# Teeth_Radiology_SCH.net
KiCad netlist of a schematic drawn in Altium Designer
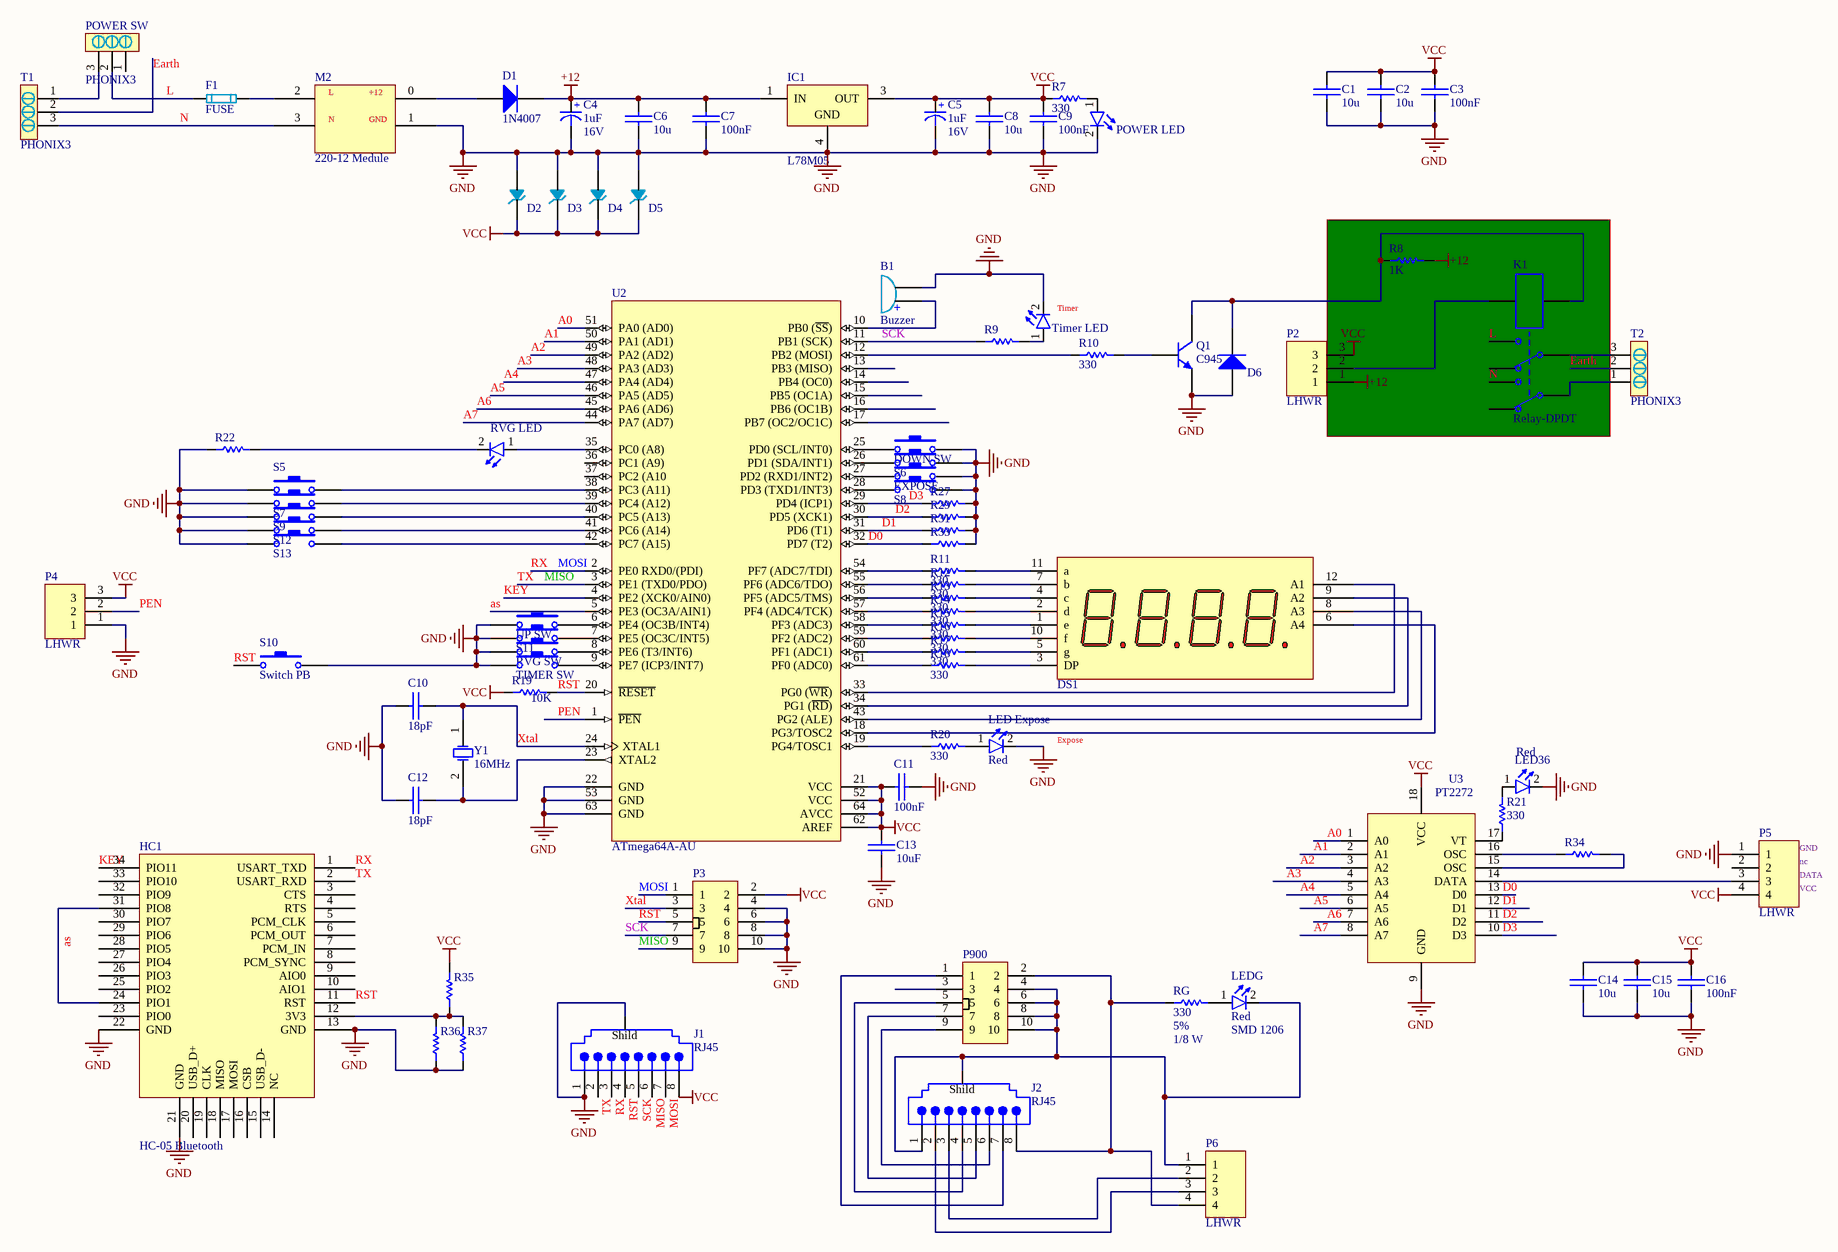
[diagram p0: Teeth_Radiology_SCH.SchDoc]

(export (version "E")
  (design (tool "Eeschema 10.0.6"))
  (components
    (comp (ref "B1")
      (value "Buzzer")
      (footprint "Buzzer")
      (fields (field (name "DESIGNER") "Hamed Jafarzadeh"))
      (libsource (lib "R2T Team Library") (part "Buzzer"))
    )
    (comp (ref "C1")
      (value "10u")
      (footprint "SMD_CAP_1206")
      (description "Bipolar Capacitor")
      (fields (field (name "VOLTAGE") "100V") (field (name "DESIGNER") "Saeid Jorablo"))
      (libsource (lib "My Library") (part "Cap-Bipolar"))
    )
    (comp (ref "C2")
      (value "10u")
      (footprint "SMD_CAP_1206")
      (description "Bipolar Capacitor")
      (fields (field (name "VOLTAGE") "100V") (field (name "DESIGNER") "Saeid Jorablo"))
      (libsource (lib "My Library") (part "Cap-Bipolar"))
    )
    (comp (ref "C3")
      (value "100nF")
      (footprint "SMD_CAP_1206")
      (description "Bipolar Capacitor")
      (fields (field (name "VOLTAGE") "100V") (field (name "DESIGNER") "Saeid Jorablo"))
      (libsource (lib "My Library") (part "Cap-Bipolar"))
    )
    (comp (ref "C4")
      (value "1uF")
      (footprint "cap 04")
      (description "Polar Capacitor")
      (fields (field (name "VOLTAGE") "16V") (field (name "DESIGNER") "Saeid Jorablo"))
      (libsource (lib "My Library") (part "Cap-Polar"))
    )
    (comp (ref "C5")
      (value "1uF")
      (footprint "cap 04")
      (description "Polar Capacitor")
      (fields (field (name "VOLTAGE") "16V") (field (name "DESIGNER") "Saeid Jorablo"))
      (libsource (lib "My Library") (part "Cap-Polar"))
    )
    (comp (ref "C6")
      (value "10u")
      (footprint "SMD_CAP_1206")
      (description "Bipolar Capacitor")
      (fields (field (name "VOLTAGE") "100V") (field (name "DESIGNER") "Saeid Jorablo"))
      (libsource (lib "My Library") (part "Cap-Bipolar"))
    )
    (comp (ref "C7")
      (value "100nF")
      (footprint "SMD_CAP_1206")
      (description "Bipolar Capacitor")
      (fields (field (name "VOLTAGE") "100V") (field (name "DESIGNER") "Saeid Jorablo"))
      (libsource (lib "My Library") (part "Cap-Bipolar"))
    )
    (comp (ref "C8")
      (value "10u")
      (footprint "SMD_CAP_1206")
      (description "Bipolar Capacitor")
      (fields (field (name "VOLTAGE") "100V") (field (name "DESIGNER") "Saeid Jorablo"))
      (libsource (lib "My Library") (part "Cap-Bipolar"))
    )
    (comp (ref "C9")
      (value "100nF")
      (footprint "SMD_CAP_1206")
      (description "Bipolar Capacitor")
      (fields (field (name "VOLTAGE") "100V") (field (name "DESIGNER") "Saeid Jorablo"))
      (libsource (lib "My Library") (part "Cap-Bipolar"))
    )
    (comp (ref "C10")
      (value "18pF")
      (footprint "SMD_CAP_0805")
      (description "Bipolar Capacitor")
      (fields (field (name "VOLTAGE") "100V") (field (name "DESIGNER") "Saeid Jorablo"))
      (libsource (lib "My Library") (part "Cap-Bipolar"))
    )
    (comp (ref "C11")
      (value "100nF")
      (footprint "SMD_CAP_0805")
      (description "Bipolar Capacitor")
      (fields (field (name "VOLTAGE") "100V") (field (name "DESIGNER") "Saeid Jorablo"))
      (libsource (lib "My Library") (part "Cap-Bipolar"))
    )
    (comp (ref "C12")
      (value "18pF")
      (footprint "SMD_CAP_0805")
      (description "Bipolar Capacitor")
      (fields (field (name "VOLTAGE") "100V") (field (name "DESIGNER") "Saeid Jorablo"))
      (libsource (lib "My Library") (part "Cap-Bipolar"))
    )
    (comp (ref "C13")
      (value "10uF")
      (footprint "SMD_CAP_1206")
      (description "Bipolar Capacitor")
      (fields (field (name "VOLTAGE") "100V") (field (name "DESIGNER") "Saeid Jorablo"))
      (libsource (lib "My Library") (part "Cap-Bipolar"))
    )
    (comp (ref "C14")
      (value "10u")
      (footprint "SMD_CAP_1206")
      (description "Bipolar Capacitor")
      (fields (field (name "VOLTAGE") "100V") (field (name "DESIGNER") "Saeid Jorablo"))
      (libsource (lib "My Library") (part "Cap-Bipolar"))
    )
    (comp (ref "C15")
      (value "10u")
      (footprint "SMD_CAP_1206")
      (description "Bipolar Capacitor")
      (fields (field (name "VOLTAGE") "100V") (field (name "DESIGNER") "Saeid Jorablo"))
      (libsource (lib "My Library") (part "Cap-Bipolar"))
    )
    (comp (ref "C16")
      (value "100nF")
      (footprint "SMD_CAP_1206")
      (description "Bipolar Capacitor")
      (fields (field (name "VOLTAGE") "100V") (field (name "DESIGNER") "Saeid Jorablo"))
      (libsource (lib "My Library") (part "Cap-Bipolar"))
    )
    (comp (ref "D1")
      (value "1N4007")
      (footprint "My_DO-41")
      (description "1 Amp Diode")
      (libsource (lib "MyAltiumLib1") (part "1N4007"))
    )
    (comp (ref "D2")
      (value "Diode Zener SMD")
      (footprint "DIOMELF3615N")
      (fields (field (name "DESIGNER") "Hamed Jafarzadeh"))
      (libsource (lib "R2T Team Library") (part "Diode Zener SMD"))
    )
    (comp (ref "D3")
      (value "Diode Zener SMD")
      (footprint "DIOMELF3615N")
      (fields (field (name "DESIGNER") "Hamed Jafarzadeh"))
      (libsource (lib "R2T Team Library") (part "Diode Zener SMD"))
    )
    (comp (ref "D4")
      (value "Diode Zener SMD")
      (footprint "DIOMELF3615N")
      (fields (field (name "DESIGNER") "Hamed Jafarzadeh"))
      (libsource (lib "R2T Team Library") (part "Diode Zener SMD"))
    )
    (comp (ref "D5")
      (value "Diode Zener SMD")
      (footprint "DIOMELF3615N")
      (fields (field (name "DESIGNER") "Hamed Jafarzadeh"))
      (libsource (lib "R2T Team Library") (part "Diode Zener SMD"))
    )
    (comp (ref "D6")
      (value "1N4007")
      (footprint "My_DO-41")
      (description "1 Amp Diode")
      (libsource (lib "MyAltiumLib1") (part "1N4007"))
    )
    (comp (ref "DOWN SW")
      (value "Switch PB")
      (footprint "Switch - Push to On")
      (description "Push Button Switch")
      (libsource (lib "Electrovolt Lib") (part "Switch PB"))
    )
    (comp (ref "DS1")
      (value "7Segment-4Digit-CA")
      (footprint "7segCA")
      (description "7-Segment Display: CA")
      (fields (field (name "PUBLISHER") "www.picpars.com") (field (name "DESIGNER") "Seyed Mohsen Ghasemain"))
      (libsource (lib "usefully_Library") (part "7Seg-4Digit-CA"))
    )
    (comp (ref "EXPOSE")
      (value "Switch PB")
      (footprint "Switch - Push to On")
      (description "Push Button Switch")
      (libsource (lib "Electrovolt Lib") (part "Switch PB"))
    )
    (comp (ref "F1") (value "FUSE") (footprint "FUSE_1") (libsource (lib "Devices") (part "FUSE")))
    (comp (ref "HC1")
      (value "HC-05 Bluetooth")
      (footprint "HC-05")
      (libsource (lib "R2T Team Library") (part "HC-05 Bluetooth"))
    )
    (comp (ref "IC1")
      (value "L78M05")
      (footprint "TO-252")
      (description "Precision 500mA Regulator")
      (libsource (lib "My Library") (part "L78M05"))
    )
    (comp (ref "J1")
      (value "RJ45")
      (footprint "My_RJ45")
      (description "Right Angle, Standard Profile, RJ45-Keyed, Flange Mount PCB Jack")
      (fields (field (name "PUBLISHER") "Altium Limited"))
      (libsource (lib "MyAltiumLib1") (part "RJ45"))
    )
    (comp (ref "J2")
      (value "RJ45")
      (footprint "My_RJ45")
      (description "Right Angle, Standard Profile, RJ45-Keyed, Flange Mount PCB Jack")
      (fields (field (name "PUBLISHER") "Altium Limited"))
      (libsource (lib "MyAltiumLib1") (part "RJ45"))
    )
    (comp (ref "K1")
      (value "Relay-DPDT")
      (footprint "My_REL_cochick")
      (description "Dual-Pole Dual-Throw Relay")
      (fields (field (name "PUBLISHER") "Altium Limited"))
      (libsource (lib "MyAltiumLib1") (part "Relay-DPDT"))
    )
    (comp (ref "LED Expose")
      (value "Red")
      (footprint "LED-3mm")
      (description "LED")
      (fields (field (name "COLOR") "Red") (field (name "DESIGNER") "Saeid Jorablo"))
      (libsource (lib "My Library") (part "LED"))
    )
    (comp (ref "LED36")
      (value "Red")
      (footprint "LED-3mm")
      (description "LED")
      (fields (field (name "COLOR") "Red") (field (name "DESIGNER") "Saeid Jorablo"))
      (libsource (lib "My Library") (part "LED"))
    )
    (comp (ref "LEDG")
      (value "Red")
      (footprint "LED-3mm")
      (description "LED")
      (fields
        (field (name "COLOR") "Red")
        (field (name "SIZE") "SMD 1206")
        (field (name "DESIGNER") "Saeid Jorablo")
      )
      (libsource (lib "My Library") (part "LED"))
    )
    (comp (ref "M2")
      (value "220-12 Medule")
      (footprint "AC-DC 220-12")
      (libsource (lib "Soga Library") (part "220-12 Medule"))
    )
    (comp (ref "P2")
      (value "LHWR")
      (footprint "Polarized Header 3")
      (fields (field (name "DESIGNER:") "Hamed Jafarzadeh - www.R2T.ir"))
      (libsource (lib "R2T Team Library") (part "3pin LHWR"))
    )
    (comp (ref "P3")
      (value "BoxHeader 2x5")
      (footprint "Box Header 2x5")
      (fields (field (name "DESIGNER") "HamedJafarzadeh - ww.R2T.ir"))
      (libsource (lib "R2T Team Library") (part "BoxHeader 2x5"))
    )
    (comp (ref "P4")
      (value "LHWR")
      (footprint "Polarized Header 3")
      (fields (field (name "DESIGNER:") "Hamed Jafarzadeh - www.R2T.ir"))
      (libsource (lib "R2T Team Library") (part "3pin LHWR"))
    )
    (comp (ref "P5")
      (value "LHWR")
      (footprint "Polarized Header 4")
      (fields (field (name "DESIGNER:") "Hamed Jafarzadeh - www.R2T.ir"))
      (libsource (lib "R2T Team Library") (part "4pin LHWR"))
    )
    (comp (ref "P6")
      (value "LHWR")
      (footprint "Polarized Header 4")
      (fields (field (name "DESIGNER:") "Hamed Jafarzadeh - www.R2T.ir"))
      (libsource (lib "R2T Team Library") (part "4pin LHWR"))
    )
    (comp (ref "P900")
      (value "BoxHeader 2x5")
      (footprint "Box Header 2x5")
      (fields (field (name "DESIGNER") "HamedJafarzadeh - ww.R2T.ir"))
      (libsource (lib "R2T Team Library") (part "BoxHeader 2x5"))
    )
    (comp (ref "POWER LED")
      (value "Red")
      (footprint "LED-3mm")
      (description "LED")
      (fields (field (name "DESIGNER") "Saeid Jorablo"))
      (libsource (lib "My Library") (part "LED"))
    )
    (comp (ref "POWER SW")
      (value "PHONIX3")
      (footprint "PHONIX3")
      (libsource (lib "My_lib_new") (part "PHONIX3"))
    )
    (comp (ref "Q1")
      (value "C945")
      (footprint "C945")
      (description "NPN Transistor")
      (fields (field (name "DESIGNER") "Saeid Jorablo"))
      (libsource (lib "Electrovolt Lib") (part "C945"))
    )
    (comp (ref "R7")
      (value "330")
      (footprint "RES 0805 (2012X06L)")
      (description "Resistor")
      (fields (field (name "TOLERANCE") "5%") (field (name "POWER") "1/8 W"))
      (libsource (lib "My Library") (part "Resistor"))
    )
    (comp (ref "R8")
      (value "1K")
      (footprint "RES 0805 (2012X06L)")
      (description "Resistor")
      (fields (field (name "TOLERANCE") "5%") (field (name "POWER") "1/8 W"))
      (libsource (lib "My Library") (part "Resistor"))
    )
    (comp (ref "R9")
      (value "330")
      (footprint "RES 0805 (2012X06L)")
      (description "Resistor")
      (fields (field (name "TOLERANCE") "5%") (field (name "POWER") "1/8 W"))
      (libsource (lib "My Library") (part "Resistor"))
    )
    (comp (ref "R10")
      (value "330")
      (footprint "RES 0805 (2012X06L)")
      (description "Resistor")
      (fields (field (name "TOLERANCE") "5%") (field (name "POWER") "1/8 W"))
      (libsource (lib "Electrovolt Lib") (part "Resistor"))
    )
    (comp (ref "R11")
      (value "330")
      (footprint "RES 0805 (2012X06L)")
      (description "Resistor")
      (fields (field (name "TOLERANCE") "5%") (field (name "POWER") "1/8 W"))
      (libsource (lib "My Library") (part "Resistor"))
    )
    (comp (ref "R12")
      (value "330")
      (footprint "RES 0805 (2012X06L)")
      (description "Resistor")
      (fields (field (name "TOLERANCE") "5%") (field (name "POWER") "1/8 W"))
      (libsource (lib "My Library") (part "Resistor"))
    )
    (comp (ref "R13")
      (value "330")
      (footprint "RES 0805 (2012X06L)")
      (description "Resistor")
      (fields (field (name "TOLERANCE") "5%") (field (name "POWER") "1/8 W"))
      (libsource (lib "My Library") (part "Resistor"))
    )
    (comp (ref "R14")
      (value "330")
      (footprint "RES 0805 (2012X06L)")
      (description "Resistor")
      (fields (field (name "TOLERANCE") "5%") (field (name "POWER") "1/8 W"))
      (libsource (lib "My Library") (part "Resistor"))
    )
    (comp (ref "R15")
      (value "330")
      (footprint "RES 0805 (2012X06L)")
      (description "Resistor")
      (fields (field (name "TOLERANCE") "5%") (field (name "POWER") "1/8 W"))
      (libsource (lib "My Library") (part "Resistor"))
    )
    (comp (ref "R16")
      (value "330")
      (footprint "RES 0805 (2012X06L)")
      (description "Resistor")
      (fields (field (name "TOLERANCE") "5%") (field (name "POWER") "1/8 W"))
      (libsource (lib "My Library") (part "Resistor"))
    )
    (comp (ref "R17")
      (value "330")
      (footprint "RES 0805 (2012X06L)")
      (description "Resistor")
      (fields (field (name "TOLERANCE") "5%") (field (name "POWER") "1/8 W"))
      (libsource (lib "My Library") (part "Resistor"))
    )
    (comp (ref "R18")
      (value "330")
      (footprint "RES 0805 (2012X06L)")
      (description "Resistor")
      (fields (field (name "TOLERANCE") "5%") (field (name "POWER") "1/8 W"))
      (libsource (lib "My Library") (part "Resistor"))
    )
    (comp (ref "R19")
      (value "10K")
      (footprint "RES 0805 (2012X06L)")
      (description "Resistor")
      (fields (field (name "TOLERANCE") "5%") (field (name "POWER") "1/8 W"))
      (libsource (lib "My Library") (part "Resistor"))
    )
    (comp (ref "R20")
      (value "330")
      (footprint "RES 0805 (2012X06L)")
      (description "Resistor")
      (fields (field (name "TOLERANCE") "5%") (field (name "POWER") "1/8 W"))
      (libsource (lib "My Library") (part "Resistor"))
    )
    (comp (ref "R21")
      (value "330")
      (footprint "RES 0805 (2012X06L)")
      (description "Resistor")
      (fields (field (name "TOLERANCE") "5%") (field (name "POWER") "1/8 W"))
      (libsource (lib "My Library") (part "Resistor"))
    )
    (comp (ref "R22")
      (value "330")
      (footprint "RES 0805 (2012X06L)")
      (description "Resistor")
      (fields (field (name "TOLERANCE") "5%") (field (name "POWER") "1/8 W"))
      (libsource (lib "My Library") (part "Resistor"))
    )
    (comp (ref "R27")
      (value "1K")
      (footprint "RES 0805 (2012X06L)")
      (description "Resistor")
      (fields (field (name "TOLERANCE") "5%") (field (name "POWER") "1/8 W"))
      (libsource (lib "My Library") (part "Resistor"))
    )
    (comp (ref "R29")
      (value "1K")
      (footprint "RES 0805 (2012X06L)")
      (description "Resistor")
      (fields (field (name "TOLERANCE") "5%") (field (name "POWER") "1/8 W"))
      (libsource (lib "My Library") (part "Resistor"))
    )
    (comp (ref "R31")
      (value "1K")
      (footprint "RES 0805 (2012X06L)")
      (description "Resistor")
      (fields (field (name "TOLERANCE") "5%") (field (name "POWER") "1/8 W"))
      (libsource (lib "My Library") (part "Resistor"))
    )
    (comp (ref "R33")
      (value "1K")
      (footprint "RES 0805 (2012X06L)")
      (description "Resistor")
      (fields (field (name "TOLERANCE") "5%") (field (name "POWER") "1/8 W"))
      (libsource (lib "My Library") (part "Resistor"))
    )
    (comp (ref "R34")
      (value "820k")
      (footprint "RES 0805 (2012X06L)")
      (description "Resistor")
      (fields (field (name "TOLERANCE") "5%") (field (name "POWER") "1/8 W"))
      (libsource (lib "My Library") (part "Resistor"))
    )
    (comp (ref "R35")
      (value "51k")
      (footprint "RES 0805 (2012X06L)")
      (description "Resistor")
      (fields (field (name "TOLERANCE") "5%") (field (name "POWER") "1/8 W"))
      (libsource (lib "My Library") (part "Resistor"))
    )
    (comp (ref "R36")
      (value "100k")
      (footprint "RES 0805 (2012X06L)")
      (description "Resistor")
      (fields (field (name "TOLERANCE") "5%") (field (name "POWER") "1/8 W"))
      (libsource (lib "My Library") (part "Resistor"))
    )
    (comp (ref "R37")
      (value "100k")
      (footprint "RES 0805 (2012X06L)")
      (description "Resistor")
      (fields (field (name "TOLERANCE") "5%") (field (name "POWER") "1/8 W"))
      (libsource (lib "My Library") (part "Resistor"))
    )
    (comp (ref "RG")
      (value "330")
      (footprint "RES 0805 (2012X06L)")
      (description "Resistor")
      (fields (field (name "TOLERANCE") "5%") (field (name "POWER") "1/8 W"))
      (libsource (lib "My Library") (part "Resistor"))
    )
    (comp (ref "RVG LED")
      (value "Red")
      (footprint "LED-3mm")
      (description "LED")
      (fields (field (name "DESIGNER") "Saeid Jorablo"))
      (libsource (lib "My Library") (part "LED"))
    )
    (comp (ref "RVG SW")
      (value "Switch PB")
      (footprint "Switch - Push to On")
      (description "Push Button Switch")
      (libsource (lib "Electrovolt Lib") (part "Switch PB"))
    )
    (comp (ref "S5")
      (value "Switch PB")
      (footprint "Switch - Push to On")
      (description "Push Button Switch")
      (libsource (lib "Electrovolt Lib") (part "Switch PB"))
    )
    (comp (ref "S6")
      (value "Switch PB")
      (footprint "Switch - Push to On")
      (description "Push Button Switch")
      (libsource (lib "Electrovolt Lib") (part "Switch PB"))
    )
    (comp (ref "S7")
      (value "Switch PB")
      (footprint "Switch - Push to On")
      (description "Push Button Switch")
      (libsource (lib "Electrovolt Lib") (part "Switch PB"))
    )
    (comp (ref "S8")
      (value "Switch PB")
      (footprint "Switch - Push to On")
      (description "Push Button Switch")
      (libsource (lib "Electrovolt Lib") (part "Switch PB"))
    )
    (comp (ref "S9")
      (value "Switch PB")
      (footprint "Switch - Push to On")
      (description "Push Button Switch")
      (libsource (lib "Electrovolt Lib") (part "Switch PB"))
    )
    (comp (ref "S10")
      (value "Switch PB")
      (footprint "Switch - Push to On")
      (description "Push Button Switch")
      (libsource (lib "Electrovolt Lib") (part "Switch PB"))
    )
    (comp (ref "S11")
      (value "Switch PB")
      (footprint "Switch - Push to On")
      (description "Push Button Switch")
      (libsource (lib "Electrovolt Lib") (part "Switch PB"))
    )
    (comp (ref "S12")
      (value "Switch PB")
      (footprint "Switch - Push to On")
      (description "Push Button Switch")
      (libsource (lib "Electrovolt Lib") (part "Switch PB"))
    )
    (comp (ref "S13")
      (value "Switch PB")
      (footprint "Switch - Push to On")
      (description "Push Button Switch")
      (libsource (lib "Electrovolt Lib") (part "Switch PB"))
    )
    (comp (ref "T1") (value "PHONIX3") (footprint "PHONIX3") (libsource (lib "") (part "PHONIX3_2")))
    (comp (ref "T2") (value "PHONIX3") (footprint "PHONIX3") (libsource (lib "") (part "PHONIX3_1")))
    (comp (ref "Timer LED")
      (value "Red")
      (footprint "LED-3mm")
      (description "LED")
      (fields (field (name "DESIGNER") "Saeid Jorablo"))
      (libsource (lib "My Library") (part "LED"))
    )
    (comp (ref "TIMER SW")
      (value "Switch PB")
      (footprint "Switch - Push to On")
      (description "Push Button Switch")
      (libsource (lib "Electrovolt Lib") (part "Switch PB"))
    )
    (comp (ref "U2")
      (value "ATmega64A-AU")
      (footprint "64A_M")
      (fields (field (name "PUBLISHER") "Altium Limited"))
      (libsource (lib "Atmel Microcontroller 8-Bit megaAVR") (part "ATmega64A-AU"))
    )
    (comp (ref "U3") (value "PT2272") (footprint "DIP18") (libsource (lib "My_lib_new") (part "PT2272")))
    (comp (ref "UP SW")
      (value "Switch PB")
      (footprint "Switch - Push to On")
      (description "Push Button Switch")
      (libsource (lib "Electrovolt Lib") (part "Switch PB"))
    )
    (comp (ref "Y1")
      (value "16MHz")
      (footprint "XTAL Small")
      (description "XTAL Crystal")
      (libsource (lib "My Library") (part "XTAL"))
    )
  )
  (nets
    (net (code "1") (name "+12") (class "Default")
      (node (ref "C4") (pin "1") (pinfunction "+_1") (pintype "passive"))
      (node (ref "C6") (pin "1") (pinfunction "+_1") (pintype "passive"))
      (node (ref "C7") (pin "1") (pinfunction "+_1") (pintype "passive"))
      (node (ref "D1") (pin "K") (pinfunction "K_K") (pintype "passive"))
      (node (ref "IC1") (pin "1") (pinfunction "IN_1") (pintype "power_in"))
      (node (ref "P2") (pin "1") (pinfunction "1_1") (pintype "passive"))
      (node (ref "R8") (pin "2") (pinfunction "2_2") (pintype "passive"))
    )
    (net (code "2") (name "/A0") (class "Default")
      (node (ref "U2") (pin "51") (pinfunction "PA0_(AD0)_51") (pintype "bidirectional"))
      (node (ref "U3") (pin "1") (pinfunction "A0_1") (pintype "passive"))
    )
    (net (code "3") (name "/A1") (class "Default")
      (node (ref "U2") (pin "50") (pinfunction "PA1_(AD1)_50") (pintype "bidirectional"))
      (node (ref "U3") (pin "2") (pinfunction "A1_2") (pintype "passive"))
    )
    (net (code "4") (name "/A2") (class "Default")
      (node (ref "U2") (pin "49") (pinfunction "PA2_(AD2)_49") (pintype "bidirectional"))
      (node (ref "U3") (pin "3") (pinfunction "A2_3") (pintype "passive"))
    )
    (net (code "5") (name "/A3") (class "Default")
      (node (ref "U2") (pin "48") (pinfunction "PA3_(AD3)_48") (pintype "bidirectional"))
      (node (ref "U3") (pin "4") (pinfunction "A3_4") (pintype "passive"))
    )
    (net (code "6") (name "/A4") (class "Default")
      (node (ref "U2") (pin "47") (pinfunction "PA4_(AD4)_47") (pintype "bidirectional"))
      (node (ref "U3") (pin "5") (pinfunction "A4_5") (pintype "passive"))
    )
    (net (code "7") (name "/A5") (class "Default")
      (node (ref "U2") (pin "46") (pinfunction "PA5_(AD5)_46") (pintype "bidirectional"))
      (node (ref "U3") (pin "6") (pinfunction "A5_6") (pintype "passive"))
    )
    (net (code "8") (name "/A6") (class "Default")
      (node (ref "U2") (pin "45") (pinfunction "PA6_(AD6)_45") (pintype "bidirectional"))
      (node (ref "U3") (pin "7") (pinfunction "A6_7") (pintype "passive"))
    )
    (net (code "9") (name "/A7") (class "Default")
      (node (ref "U2") (pin "44") (pinfunction "PA7_(AD7)_44") (pintype "bidirectional"))
      (node (ref "U3") (pin "8") (pinfunction "A7_8") (pintype "passive"))
    )
    (net (code "10") (name "/D0") (class "Default")
      (node (ref "R33") (pin "1") (pinfunction "1_1") (pintype "passive"))
      (node (ref "U2") (pin "32") (pinfunction "PD7_(T2)_32") (pintype "bidirectional"))
      (node (ref "U3") (pin "13") (pinfunction "D0_13") (pintype "passive"))
    )
    (net (code "11") (name "/D1") (class "Default")
      (node (ref "R31") (pin "1") (pinfunction "1_1") (pintype "passive"))
      (node (ref "U2") (pin "31") (pinfunction "PD6_(T1)_31") (pintype "bidirectional"))
      (node (ref "U3") (pin "12") (pinfunction "D1_12") (pintype "passive"))
    )
    (net (code "12") (name "/D2") (class "Default")
      (node (ref "R29") (pin "1") (pinfunction "1_1") (pintype "passive"))
      (node (ref "U2") (pin "30") (pinfunction "PD5_(XCK1)_30") (pintype "bidirectional"))
      (node (ref "U3") (pin "11") (pinfunction "D2_11") (pintype "passive"))
    )
    (net (code "13") (name "/D3") (class "Default")
      (node (ref "R27") (pin "1") (pinfunction "1_1") (pintype "passive"))
      (node (ref "U2") (pin "29") (pinfunction "PD4_(ICP1)_29") (pintype "bidirectional"))
      (node (ref "U3") (pin "10") (pinfunction "D3_10") (pintype "passive"))
    )
    (net (code "14") (name "/Earth") (class "Default")
      (node (ref "T1") (pin "2") (pintype "passive"))
      (node (ref "T2") (pin "2") (pintype "passive"))
    )
    (net (code "15") (name "/KEY") (class "Default")
      (node (ref "HC1") (pin "34") (pinfunction "PIO11_34") (pintype "passive"))
      (node (ref "U2") (pin "4") (pinfunction "PE2_(XCK0/AIN0)_4") (pintype "bidirectional"))
    )
    (net (code "16") (name "/L") (class "Default")
      (node (ref "F1") (pin "1") (pintype "passive"))
      (node (ref "K1") (pin "S1") (pinfunction "S1_S1") (pintype "passive"))
      (node (ref "POWER SW") (pin "2") (pintype "passive"))
    )
    (net (code "17") (name "/MISO") (class "Default")
      (node (ref "HC1") (pin "2") (pinfunction "USART_RXD_2") (pintype "passive"))
      (node (ref "J1") (pin "2") (pinfunction "2_2") (pintype "passive"))
      (node (ref "J1") (pin "6") (pinfunction "6_6") (pintype "passive"))
      (node (ref "P3") (pin "9") (pinfunction "9_9") (pintype "passive"))
      (node (ref "U2") (pin "3") (pinfunction "PE1_(TXD0/PDO)_3") (pintype "bidirectional"))
    )
    (net (code "18") (name "/MOSI") (class "Default")
      (node (ref "HC1") (pin "1") (pinfunction "USART_TXD_1") (pintype "passive"))
      (node (ref "J1") (pin "3") (pinfunction "3_3") (pintype "passive"))
      (node (ref "J1") (pin "7") (pinfunction "7_7") (pintype "passive"))
      (node (ref "P3") (pin "1") (pinfunction "1_1") (pintype "passive"))
      (node (ref "U2") (pin "2") (pinfunction "PE0_RXD0/(PDI)_2") (pintype "bidirectional"))
    )
    (net (code "19") (name "/N") (class "Default")
      (node (ref "K1") (pin "S2") (pinfunction "S2_S2") (pintype "passive"))
      (node (ref "M2") (pin "3") (pinfunction "3_3") (pintype "passive"))
      (node (ref "T1") (pin "3") (pintype "passive"))
    )
    (net (code "20") (name "/PEN") (class "Default")
      (node (ref "P4") (pin "2") (pinfunction "2_2") (pintype "passive"))
      (node (ref "U2") (pin "1") (pinfunction "~{PEN}_1") (pintype "input"))
    )
    (net (code "21") (name "/RST") (class "Default")
      (node (ref "HC1") (pin "11") (pinfunction "RST_11") (pintype "passive"))
      (node (ref "J1") (pin "4") (pinfunction "4_4") (pintype "passive"))
      (node (ref "P3") (pin "5") (pinfunction "5_5") (pintype "passive"))
      (node (ref "R19") (pin "2") (pinfunction "2_2") (pintype "passive"))
      (node (ref "S10") (pin "1") (pinfunction "1_1") (pintype "passive"))
      (node (ref "U2") (pin "20") (pinfunction "~{RESET}_20") (pintype "input"))
    )
    (net (code "22") (name "/SCK") (class "Default")
      (node (ref "J1") (pin "5") (pinfunction "5_5") (pintype "passive"))
      (node (ref "P3") (pin "7") (pinfunction "7_7") (pintype "passive"))
      (node (ref "R9") (pin "1") (pinfunction "1_1") (pintype "passive"))
      (node (ref "U2") (pin "11") (pinfunction "PB1_(SCK)_11") (pintype "bidirectional"))
    )
    (net (code "23") (name "/Xtal") (class "Default")
      (node (ref "C10") (pin "2") (pinfunction "-_2") (pintype "passive"))
      (node (ref "P3") (pin "3") (pinfunction "3_3") (pintype "passive"))
      (node (ref "U2") (pin "24") (pinfunction "XTAL1_24") (pintype "input"))
      (node (ref "Y1") (pin "1") (pinfunction "OSC1_1") (pintype "passive"))
    )
    (net (code "24") (name "/as") (class "Default")
      (node (ref "HC1") (pin "24") (pinfunction "PIO1_24") (pintype "passive"))
      (node (ref "HC1") (pin "31") (pinfunction "PIO8_31") (pintype "passive"))
      (node (ref "U2") (pin "5") (pinfunction "PE3_(OC3A/AIN1)_5") (pintype "bidirectional"))
    )
    (net (code "25") (name "GND") (class "Default")
      (node (ref "B1") (pin "2") (pinfunction "GND_2") (pintype "passive"))
      (node (ref "C1") (pin "2") (pinfunction "-_2") (pintype "passive"))
      (node (ref "C10") (pin "1") (pinfunction "+_1") (pintype "passive"))
      (node (ref "C11") (pin "1") (pinfunction "+_1") (pintype "passive"))
      (node (ref "C12") (pin "1") (pinfunction "+_1") (pintype "passive"))
      (node (ref "C13") (pin "2") (pinfunction "-_2") (pintype "passive"))
      (node (ref "C14") (pin "2") (pinfunction "-_2") (pintype "passive"))
      (node (ref "C15") (pin "2") (pinfunction "-_2") (pintype "passive"))
      (node (ref "C16") (pin "2") (pinfunction "-_2") (pintype "passive"))
      (node (ref "C2") (pin "2") (pinfunction "-_2") (pintype "passive"))
      (node (ref "C3") (pin "2") (pinfunction "-_2") (pintype "passive"))
      (node (ref "C4") (pin "2") (pinfunction "-_2") (pintype "passive"))
      (node (ref "C5") (pin "2") (pinfunction "-_2") (pintype "passive"))
      (node (ref "C6") (pin "2") (pinfunction "-_2") (pintype "passive"))
      (node (ref "C7") (pin "2") (pinfunction "-_2") (pintype "passive"))
      (node (ref "C8") (pin "2") (pinfunction "-_2") (pintype "passive"))
      (node (ref "C9") (pin "2") (pinfunction "-_2") (pintype "passive"))
      (node (ref "D2") (pin "2") (pintype "passive"))
      (node (ref "D3") (pin "2") (pintype "passive"))
      (node (ref "D4") (pin "2") (pintype "passive"))
      (node (ref "D5") (pin "2") (pintype "passive"))
      (node (ref "D6") (pin "A") (pinfunction "A_A") (pintype "passive"))
      (node (ref "DOWN SW") (pin "2") (pinfunction "2_2") (pintype "passive"))
      (node (ref "EXPOSE") (pin "2") (pinfunction "2_2") (pintype "passive"))
      (node (ref "HC1") (pin "13") (pinfunction "GND_13") (pintype "passive"))
      (node (ref "HC1") (pin "21") (pinfunction "GND_21") (pintype "passive"))
      (node (ref "HC1") (pin "22") (pinfunction "GND_22") (pintype "passive"))
      (node (ref "IC1") (pin "4") (pinfunction "GND_4") (pintype "power_in"))
      (node (ref "J1") (pin "1") (pinfunction "1_1") (pintype "passive"))
      (node (ref "J1") (pin "shild") (pinfunction "Shild_shild") (pintype "passive"))
      (node (ref "LED Expose") (pin "2") (pinfunction "K_2") (pintype "passive"))
      (node (ref "LED36") (pin "2") (pinfunction "K_2") (pintype "passive"))
      (node (ref "M2") (pin "1") (pinfunction "1_1") (pintype "passive"))
      (node (ref "P3") (pin "10") (pinfunction "10_10") (pintype "passive"))
      (node (ref "P3") (pin "4") (pinfunction "4_4") (pintype "passive"))
      (node (ref "P3") (pin "6") (pinfunction "6_6") (pintype "passive"))
      (node (ref "P3") (pin "8") (pinfunction "8_8") (pintype "passive"))
      (node (ref "P4") (pin "1") (pinfunction "1_1") (pintype "passive"))
      (node (ref "P5") (pin "1") (pinfunction "1_1") (pintype "passive"))
      (node (ref "POWER LED") (pin "2") (pinfunction "K_2") (pintype "passive"))
      (node (ref "Q1") (pin "1") (pinfunction "E_1") (pintype "passive"))
      (node (ref "R22") (pin "1") (pinfunction "1_1") (pintype "passive"))
      (node (ref "R27") (pin "2") (pinfunction "2_2") (pintype "passive"))
      (node (ref "R29") (pin "2") (pinfunction "2_2") (pintype "passive"))
      (node (ref "R31") (pin "2") (pinfunction "2_2") (pintype "passive"))
      (node (ref "R33") (pin "2") (pinfunction "2_2") (pintype "passive"))
      (node (ref "R36") (pin "1") (pinfunction "1_1") (pintype "passive"))
      (node (ref "R37") (pin "1") (pinfunction "1_1") (pintype "passive"))
      (node (ref "RVG SW") (pin "1") (pinfunction "1_1") (pintype "passive"))
      (node (ref "S10") (pin "2") (pinfunction "2_2") (pintype "passive"))
      (node (ref "S11") (pin "1") (pinfunction "1_1") (pintype "passive"))
      (node (ref "S12") (pin "1") (pinfunction "1_1") (pintype "passive"))
      (node (ref "S13") (pin "1") (pinfunction "1_1") (pintype "passive"))
      (node (ref "S5") (pin "1") (pinfunction "1_1") (pintype "passive"))
      (node (ref "S6") (pin "2") (pinfunction "2_2") (pintype "passive"))
      (node (ref "S7") (pin "1") (pinfunction "1_1") (pintype "passive"))
      (node (ref "S8") (pin "2") (pinfunction "2_2") (pintype "passive"))
      (node (ref "S9") (pin "1") (pinfunction "1_1") (pintype "passive"))
      (node (ref "TIMER SW") (pin "1") (pinfunction "1_1") (pintype "passive"))
      (node (ref "Timer LED") (pin "2") (pinfunction "K_2") (pintype "passive"))
      (node (ref "U2") (pin "22") (pinfunction "GND_22") (pintype "power_in"))
      (node (ref "U2") (pin "53") (pinfunction "GND_53") (pintype "power_in"))
      (node (ref "U2") (pin "63") (pinfunction "GND_63") (pintype "power_in"))
      (node (ref "U3") (pin "9") (pinfunction "GND_9") (pintype "passive"))
      (node (ref "UP SW") (pin "1") (pinfunction "1_1") (pintype "passive"))
    )
    (net (code "26") (name "Net-(B1-VCC)") (class "Default")
      (node (ref "B1") (pin "1") (pinfunction "VCC_1") (pintype "passive"))
      (node (ref "U2") (pin "10") (pinfunction "PB0_(~{SS})_10") (pintype "bidirectional"))
    )
    (net (code "27") (name "Net-(C12--)") (class "Default")
      (node (ref "C12") (pin "2") (pinfunction "-_2") (pintype "passive"))
      (node (ref "U2") (pin "23") (pinfunction "XTAL2_23") (pintype "output"))
      (node (ref "Y1") (pin "2") (pinfunction "OSC2_2") (pintype "passive"))
    )
    (net (code "28") (name "Net-(D1-PadA)") (class "Default")
      (node (ref "D1") (pin "A") (pinfunction "A_A") (pintype "passive"))
      (node (ref "M2") (pin "0") (pinfunction "0_0") (pintype "passive"))
    )
    (net (code "29") (name "Net-(DS1-A1)") (class "Default")
      (node (ref "DS1") (pin "12") (pinfunction "A1_12") (pintype "passive"))
      (node (ref "U2") (pin "33") (pinfunction "PG0_(~{WR})_33") (pintype "bidirectional"))
    )
    (net (code "30") (name "Net-(DS1-A2)") (class "Default")
      (node (ref "DS1") (pin "9") (pinfunction "A2_9") (pintype "passive"))
      (node (ref "U2") (pin "34") (pinfunction "PG1_(~{RD})_34") (pintype "bidirectional"))
    )
    (net (code "31") (name "Net-(DS1-A3)") (class "Default")
      (node (ref "DS1") (pin "8") (pinfunction "A3_8") (pintype "passive"))
      (node (ref "U2") (pin "43") (pinfunction "PG2_(ALE)_43") (pintype "bidirectional"))
    )
    (net (code "32") (name "Net-(DS1-A4)") (class "Default")
      (node (ref "DS1") (pin "6") (pinfunction "A4_6") (pintype "passive"))
      (node (ref "U2") (pin "18") (pinfunction "PG3/TOSC2_18") (pintype "bidirectional"))
    )
    (net (code "33") (name "Net-(DS1-DP)") (class "Default")
      (node (ref "DS1") (pin "3") (pinfunction "DP_3") (pintype "passive"))
      (node (ref "R18") (pin "2") (pinfunction "2_2") (pintype "passive"))
    )
    (net (code "34") (name "Net-(DS1-a)") (class "Default")
      (node (ref "DS1") (pin "11") (pinfunction "a_11") (pintype "passive"))
      (node (ref "R11") (pin "2") (pinfunction "2_2") (pintype "passive"))
    )
    (net (code "35") (name "Net-(DS1-b)") (class "Default")
      (node (ref "DS1") (pin "7") (pinfunction "b_7") (pintype "passive"))
      (node (ref "R12") (pin "2") (pinfunction "2_2") (pintype "passive"))
    )
    (net (code "36") (name "Net-(DS1-c)") (class "Default")
      (node (ref "DS1") (pin "4") (pinfunction "c_4") (pintype "passive"))
      (node (ref "R13") (pin "2") (pinfunction "2_2") (pintype "passive"))
    )
    (net (code "37") (name "Net-(DS1-d)") (class "Default")
      (node (ref "DS1") (pin "2") (pinfunction "d_2") (pintype "passive"))
      (node (ref "R14") (pin "2") (pinfunction "2_2") (pintype "passive"))
    )
    (net (code "38") (name "Net-(DS1-e)") (class "Default")
      (node (ref "DS1") (pin "1") (pinfunction "e_1") (pintype "passive"))
      (node (ref "R15") (pin "2") (pinfunction "2_2") (pintype "passive"))
    )
    (net (code "39") (name "Net-(DS1-f)") (class "Default")
      (node (ref "DS1") (pin "10") (pinfunction "f_10") (pintype "passive"))
      (node (ref "R16") (pin "2") (pinfunction "2_2") (pintype "passive"))
    )
    (net (code "40") (name "Net-(DS1-g)") (class "Default")
      (node (ref "DS1") (pin "5") (pinfunction "g_5") (pintype "passive"))
      (node (ref "R17") (pin "2") (pinfunction "2_2") (pintype "passive"))
    )
    (net (code "41") (name "Net-(F1-Pad2)") (class "Default")
      (node (ref "F1") (pin "2") (pintype "passive"))
      (node (ref "M2") (pin "2") (pinfunction "2_2") (pintype "passive"))
    )
    (net (code "42") (name "Net-(HC1-3V3)") (class "Default")
      (node (ref "HC1") (pin "12") (pinfunction "3V3_12") (pintype "passive"))
      (node (ref "R35") (pin "1") (pinfunction "1_1") (pintype "passive"))
      (node (ref "R36") (pin "2") (pinfunction "2_2") (pintype "passive"))
      (node (ref "R37") (pin "2") (pinfunction "2_2") (pintype "passive"))
    )
    (net (code "43") (name "Net-(J2-Pad2)") (class "Default")
      (node (ref "J2") (pin "2") (pinfunction "2_2") (pintype "passive"))
      (node (ref "P6") (pin "3") (pinfunction "3_3") (pintype "passive"))
    )
    (net (code "44") (name "Net-(J2-Pad3)") (class "Default")
      (node (ref "J2") (pin "3") (pinfunction "3_3") (pintype "passive"))
      (node (ref "P6") (pin "2") (pinfunction "2_2") (pintype "passive"))
    )
    (net (code "45") (name "Net-(J2-Pad4)") (class "Default")
      (node (ref "J2") (pin "4") (pinfunction "4_4") (pintype "passive"))
      (node (ref "P900") (pin "5") (pinfunction "5_5") (pintype "passive"))
    )
    (net (code "46") (name "Net-(J2-Pad5)") (class "Default")
      (node (ref "J2") (pin "5") (pinfunction "5_5") (pintype "passive"))
      (node (ref "P900") (pin "7") (pinfunction "7_7") (pintype "passive"))
    )
    (net (code "47") (name "Net-(J2-Pad6)") (class "Default")
      (node (ref "J2") (pin "6") (pinfunction "6_6") (pintype "passive"))
      (node (ref "P900") (pin "9") (pinfunction "9_9") (pintype "passive"))
    )
    (net (code "48") (name "Net-(J2-Pad7)") (class "Default")
      (node (ref "J2") (pin "7") (pinfunction "7_7") (pintype "passive"))
      (node (ref "P900") (pin "1") (pinfunction "1_1") (pintype "passive"))
    )
    (net (code "49") (name "Net-(J2-Pad8)") (class "Default")
      (node (ref "J2") (pin "8") (pinfunction "8_8") (pintype "passive"))
      (node (ref "P6") (pin "4") (pinfunction "4_4") (pintype "passive"))
      (node (ref "P900") (pin "2") (pinfunction "2_2") (pintype "passive"))
      (node (ref "RG") (pin "1") (pinfunction "1_1") (pintype "passive"))
    )
    (net (code "50") (name "Net-(J2-Shild)") (class "Default")
      (node (ref "J2") (pin "1") (pinfunction "1_1") (pintype "passive"))
      (node (ref "J2") (pin "shild") (pinfunction "Shild_shild") (pintype "passive"))
      (node (ref "LEDG") (pin "2") (pinfunction "K_2") (pintype "passive"))
      (node (ref "P6") (pin "1") (pinfunction "1_1") (pintype "passive"))
      (node (ref "P900") (pin "10") (pinfunction "10_10") (pintype "passive"))
      (node (ref "P900") (pin "4") (pinfunction "4_4") (pintype "passive"))
      (node (ref "P900") (pin "6") (pinfunction "6_6") (pintype "passive"))
      (node (ref "P900") (pin "8") (pinfunction "8_8") (pintype "passive"))
    )
    (net (code "51") (name "Net-(K1-Pad2)") (class "Default")
      (node (ref "K1") (pin "2") (pinfunction "2_2") (pintype "passive"))
      (node (ref "P2") (pin "2") (pinfunction "2_2") (pintype "passive"))
    )
    (net (code "52") (name "Net-(K1-PadP1)") (class "Default")
      (node (ref "K1") (pin "P1") (pinfunction "P1_P1") (pintype "passive"))
      (node (ref "T2") (pin "3") (pintype "passive"))
    )
    (net (code "53") (name "Net-(K1-PadP2)") (class "Default")
      (node (ref "K1") (pin "P2") (pinfunction "P2_P2") (pintype "passive"))
      (node (ref "T2") (pin "1") (pintype "passive"))
    )
    (net (code "54") (name "Net-(LED Expose-A)") (class "Default")
      (node (ref "LED Expose") (pin "1") (pinfunction "A_1") (pintype "passive"))
      (node (ref "R20") (pin "2") (pinfunction "2_2") (pintype "passive"))
    )
    (net (code "55") (name "Net-(LED36-A)") (class "Default")
      (node (ref "LED36") (pin "1") (pinfunction "A_1") (pintype "passive"))
      (node (ref "R21") (pin "2") (pinfunction "2_2") (pintype "passive"))
    )
    (net (code "56") (name "Net-(LEDG-A)") (class "Default")
      (node (ref "LEDG") (pin "1") (pinfunction "A_1") (pintype "passive"))
      (node (ref "RG") (pin "2") (pinfunction "2_2") (pintype "passive"))
    )
    (net (code "57") (name "Net-(POWER LED-A)") (class "Default")
      (node (ref "POWER LED") (pin "1") (pinfunction "A_1") (pintype "passive"))
      (node (ref "R7") (pin "2") (pinfunction "2_2") (pintype "passive"))
    )
    (net (code "58") (name "Net-(POWER SW-Pad3)") (class "Default")
      (node (ref "POWER SW") (pin "3") (pintype "passive"))
      (node (ref "T1") (pin "1") (pintype "passive"))
    )
    (net (code "59") (name "Net-(Q1-B)") (class "Default")
      (node (ref "Q1") (pin "3") (pinfunction "B_3") (pintype "passive"))
      (node (ref "R10") (pin "2") (pinfunction "2_2") (pintype "passive"))
    )
    (net (code "60") (name "Net-(Q1-C)") (class "Default")
      (node (ref "D6") (pin "K") (pinfunction "K_K") (pintype "passive"))
      (node (ref "K1") (pin "1") (pinfunction "1_1") (pintype "passive"))
      (node (ref "Q1") (pin "2") (pinfunction "C_2") (pintype "passive"))
      (node (ref "R8") (pin "1") (pinfunction "1_1") (pintype "passive"))
    )
    (net (code "61") (name "Net-(R34-Pad1)") (class "Default")
      (node (ref "R34") (pin "1") (pinfunction "1_1") (pintype "passive"))
      (node (ref "U3") (pin "16") (pinfunction "OSC_16") (pintype "passive"))
    )
    (net (code "62") (name "Net-(R34-Pad2)") (class "Default")
      (node (ref "R34") (pin "2") (pinfunction "2_2") (pintype "passive"))
      (node (ref "U3") (pin "15") (pinfunction "OSC_15") (pintype "passive"))
    )
    (net (code "63") (name "Net-(RVG LED-A)") (class "Default")
      (node (ref "RVG LED") (pin "1") (pinfunction "A_1") (pintype "passive"))
      (node (ref "U2") (pin "35") (pinfunction "PC0_(A8)_35") (pintype "bidirectional"))
    )
    (net (code "64") (name "Net-(RVG LED-K)") (class "Default")
      (node (ref "R22") (pin "2") (pinfunction "2_2") (pintype "passive"))
      (node (ref "RVG LED") (pin "2") (pinfunction "K_2") (pintype "passive"))
    )
    (net (code "65") (name "Net-(Timer LED-A)") (class "Default")
      (node (ref "R9") (pin "2") (pinfunction "2_2") (pintype "passive"))
      (node (ref "Timer LED") (pin "1") (pinfunction "A_1") (pintype "passive"))
    )
    (net (code "66") (name "Net-(U2-PB2_(MOSI))") (class "Default")
      (node (ref "R10") (pin "1") (pinfunction "1_1") (pintype "passive"))
      (node (ref "U2") (pin "12") (pinfunction "PB2_(MOSI)_12") (pintype "bidirectional"))
    )
    (net (code "67") (name "Net-(U2-PC3_(A11))") (class "Default")
      (node (ref "S5") (pin "2") (pinfunction "2_2") (pintype "passive"))
      (node (ref "U2") (pin "38") (pinfunction "PC3_(A11)_38") (pintype "bidirectional"))
    )
    (net (code "68") (name "Net-(U2-PC4_(A12))") (class "Default")
      (node (ref "S7") (pin "2") (pinfunction "2_2") (pintype "passive"))
      (node (ref "U2") (pin "39") (pinfunction "PC4_(A12)_39") (pintype "bidirectional"))
    )
    (net (code "69") (name "Net-(U2-PC5_(A13))") (class "Default")
      (node (ref "S9") (pin "2") (pinfunction "2_2") (pintype "passive"))
      (node (ref "U2") (pin "40") (pinfunction "PC5_(A13)_40") (pintype "bidirectional"))
    )
    (net (code "70") (name "Net-(U2-PC6_(A14))") (class "Default")
      (node (ref "S12") (pin "2") (pinfunction "2_2") (pintype "passive"))
      (node (ref "U2") (pin "41") (pinfunction "PC6_(A14)_41") (pintype "bidirectional"))
    )
    (net (code "71") (name "Net-(U2-PC7_(A15))") (class "Default")
      (node (ref "S13") (pin "2") (pinfunction "2_2") (pintype "passive"))
      (node (ref "U2") (pin "42") (pinfunction "PC7_(A15)_42") (pintype "bidirectional"))
    )
    (net (code "72") (name "Net-(U2-PD0_(SCL{slash}INT0))") (class "Default")
      (node (ref "DOWN SW") (pin "1") (pinfunction "1_1") (pintype "passive"))
      (node (ref "U2") (pin "25") (pinfunction "PD0_(SCL/INT0)_25") (pintype "bidirectional"))
    )
    (net (code "73") (name "Net-(U2-PD1_(SDA{slash}INT1))") (class "Default")
      (node (ref "S6") (pin "1") (pinfunction "1_1") (pintype "passive"))
      (node (ref "U2") (pin "26") (pinfunction "PD1_(SDA/INT1)_26") (pintype "bidirectional"))
    )
    (net (code "74") (name "Net-(U2-PD2_(RXD1{slash}INT2))") (class "Default")
      (node (ref "EXPOSE") (pin "1") (pinfunction "1_1") (pintype "passive"))
      (node (ref "U2") (pin "27") (pinfunction "PD2_(RXD1/INT2)_27") (pintype "bidirectional"))
    )
    (net (code "75") (name "Net-(U2-PD3_(TXD1{slash}INT3))") (class "Default")
      (node (ref "S8") (pin "1") (pinfunction "1_1") (pintype "passive"))
      (node (ref "U2") (pin "28") (pinfunction "PD3_(TXD1/INT3)_28") (pintype "bidirectional"))
    )
    (net (code "76") (name "Net-(U2-PE4_(OC3B{slash}INT4))") (class "Default")
      (node (ref "U2") (pin "6") (pinfunction "PE4_(OC3B/INT4)_6") (pintype "bidirectional"))
      (node (ref "UP SW") (pin "2") (pinfunction "2_2") (pintype "passive"))
    )
    (net (code "77") (name "Net-(U2-PE5_(OC3C{slash}INT5))") (class "Default")
      (node (ref "S11") (pin "2") (pinfunction "2_2") (pintype "passive"))
      (node (ref "U2") (pin "7") (pinfunction "PE5_(OC3C/INT5)_7") (pintype "bidirectional"))
    )
    (net (code "78") (name "Net-(U2-PE6_(T3{slash}INT6))") (class "Default")
      (node (ref "RVG SW") (pin "2") (pinfunction "2_2") (pintype "passive"))
      (node (ref "U2") (pin "8") (pinfunction "PE6_(T3/INT6)_8") (pintype "bidirectional"))
    )
    (net (code "79") (name "Net-(U2-PE7_(ICP3{slash}INT7))") (class "Default")
      (node (ref "TIMER SW") (pin "2") (pinfunction "2_2") (pintype "passive"))
      (node (ref "U2") (pin "9") (pinfunction "PE7_(ICP3/INT7)_9") (pintype "bidirectional"))
    )
    (net (code "80") (name "Net-(U2-PF0_(ADC0))") (class "Default")
      (node (ref "R18") (pin "1") (pinfunction "1_1") (pintype "passive"))
      (node (ref "U2") (pin "61") (pinfunction "PF0_(ADC0)_61") (pintype "bidirectional"))
    )
    (net (code "81") (name "Net-(U2-PF1_(ADC1))") (class "Default")
      (node (ref "R17") (pin "1") (pinfunction "1_1") (pintype "passive"))
      (node (ref "U2") (pin "60") (pinfunction "PF1_(ADC1)_60") (pintype "bidirectional"))
    )
    (net (code "82") (name "Net-(U2-PF2_(ADC2))") (class "Default")
      (node (ref "R16") (pin "1") (pinfunction "1_1") (pintype "passive"))
      (node (ref "U2") (pin "59") (pinfunction "PF2_(ADC2)_59") (pintype "bidirectional"))
    )
    (net (code "83") (name "Net-(U2-PF3_(ADC3))") (class "Default")
      (node (ref "R15") (pin "1") (pinfunction "1_1") (pintype "passive"))
      (node (ref "U2") (pin "58") (pinfunction "PF3_(ADC3)_58") (pintype "bidirectional"))
    )
    (net (code "84") (name "Net-(U2-PF4_(ADC4{slash}TCK))") (class "Default")
      (node (ref "R14") (pin "1") (pinfunction "1_1") (pintype "passive"))
      (node (ref "U2") (pin "57") (pinfunction "PF4_(ADC4/TCK)_57") (pintype "bidirectional"))
    )
    (net (code "85") (name "Net-(U2-PF5_(ADC5{slash}TMS))") (class "Default")
      (node (ref "R13") (pin "1") (pinfunction "1_1") (pintype "passive"))
      (node (ref "U2") (pin "56") (pinfunction "PF5_(ADC5/TMS)_56") (pintype "bidirectional"))
    )
    (net (code "86") (name "Net-(U2-PF6_(ADC6{slash}TDO))") (class "Default")
      (node (ref "R12") (pin "1") (pinfunction "1_1") (pintype "passive"))
      (node (ref "U2") (pin "55") (pinfunction "PF6_(ADC6/TDO)_55") (pintype "bidirectional"))
    )
    (net (code "87") (name "Net-(U2-PF7_(ADC7{slash}TDI))") (class "Default")
      (node (ref "R11") (pin "1") (pinfunction "1_1") (pintype "passive"))
      (node (ref "U2") (pin "54") (pinfunction "PF7_(ADC7/TDI)_54") (pintype "bidirectional"))
    )
    (net (code "88") (name "Net-(U2-PG4{slash}TOSC1)") (class "Default")
      (node (ref "R20") (pin "1") (pinfunction "1_1") (pintype "passive"))
      (node (ref "U2") (pin "19") (pinfunction "PG4/TOSC1_19") (pintype "bidirectional"))
    )
    (net (code "89") (name "Net-(U3-DATA)") (class "Default")
      (node (ref "P5") (pin "3") (pinfunction "3_3") (pintype "passive"))
      (node (ref "U3") (pin "14") (pinfunction "DATA_14") (pintype "passive"))
    )
    (net (code "90") (name "Net-(U3-VT)") (class "Default")
      (node (ref "R21") (pin "1") (pinfunction "1_1") (pintype "passive"))
      (node (ref "U3") (pin "17") (pinfunction "VT_17") (pintype "passive"))
    )
    (net (code "91") (name "VCC") (class "Default")
      (node (ref "C1") (pin "1") (pinfunction "+_1") (pintype "passive"))
      (node (ref "C11") (pin "2") (pinfunction "-_2") (pintype "passive"))
      (node (ref "C13") (pin "1") (pinfunction "+_1") (pintype "passive"))
      (node (ref "C14") (pin "1") (pinfunction "+_1") (pintype "passive"))
      (node (ref "C15") (pin "1") (pinfunction "+_1") (pintype "passive"))
      (node (ref "C16") (pin "1") (pinfunction "+_1") (pintype "passive"))
      (node (ref "C2") (pin "1") (pinfunction "+_1") (pintype "passive"))
      (node (ref "C3") (pin "1") (pinfunction "+_1") (pintype "passive"))
      (node (ref "C5") (pin "1") (pinfunction "+_1") (pintype "passive"))
      (node (ref "C8") (pin "1") (pinfunction "+_1") (pintype "passive"))
      (node (ref "C9") (pin "1") (pinfunction "+_1") (pintype "passive"))
      (node (ref "D2") (pin "1") (pintype "passive"))
      (node (ref "D3") (pin "1") (pintype "passive"))
      (node (ref "D4") (pin "1") (pintype "passive"))
      (node (ref "D5") (pin "1") (pintype "passive"))
      (node (ref "IC1") (pin "3") (pinfunction "OUT_3") (pintype "power_in"))
      (node (ref "J1") (pin "8") (pinfunction "8_8") (pintype "passive"))
      (node (ref "P2") (pin "3") (pinfunction "3_3") (pintype "passive"))
      (node (ref "P3") (pin "2") (pinfunction "2_2") (pintype "passive"))
      (node (ref "P4") (pin "3") (pinfunction "3_3") (pintype "passive"))
      (node (ref "P5") (pin "4") (pinfunction "4_4") (pintype "passive"))
      (node (ref "R19") (pin "1") (pinfunction "1_1") (pintype "passive"))
      (node (ref "R35") (pin "2") (pinfunction "2_2") (pintype "passive"))
      (node (ref "R7") (pin "1") (pinfunction "1_1") (pintype "passive"))
      (node (ref "U2") (pin "21") (pinfunction "VCC_21") (pintype "power_in"))
      (node (ref "U2") (pin "52") (pinfunction "VCC_52") (pintype "power_in"))
      (node (ref "U2") (pin "62") (pinfunction "AREF_62") (pintype "power_in"))
      (node (ref "U2") (pin "64") (pinfunction "AVCC_64") (pintype "power_in"))
      (node (ref "U3") (pin "18") (pinfunction "VCC_18") (pintype "passive"))
    )
    (net (code "92") (name "unconnected-(HC1-AIO0-Pad9)") (class "Default")
      (node (ref "HC1") (pin "9") (pinfunction "AIO0_9") (pintype "passive"))
    )
    (net (code "93") (name "unconnected-(HC1-AIO1-Pad10)") (class "Default")
      (node (ref "HC1") (pin "10") (pinfunction "AIO1_10") (pintype "passive"))
    )
    (net (code "94") (name "unconnected-(HC1-CLK-Pad19)") (class "Default")
      (node (ref "HC1") (pin "19") (pinfunction "CLK_19") (pintype "passive"))
    )
    (net (code "95") (name "unconnected-(HC1-CSB-Pad16)") (class "Default")
      (node (ref "HC1") (pin "16") (pinfunction "CSB_16") (pintype "passive"))
    )
    (net (code "96") (name "unconnected-(HC1-CTS-Pad3)") (class "Default")
      (node (ref "HC1") (pin "3") (pinfunction "CTS_3") (pintype "passive"))
    )
    (net (code "97") (name "unconnected-(HC1-MISO-Pad18)") (class "Default")
      (node (ref "HC1") (pin "18") (pinfunction "MISO_18") (pintype "passive"))
    )
    (net (code "98") (name "unconnected-(HC1-MOSI-Pad17)") (class "Default")
      (node (ref "HC1") (pin "17") (pinfunction "MOSI_17") (pintype "passive"))
    )
    (net (code "99") (name "unconnected-(HC1-NC-Pad14)") (class "Default")
      (node (ref "HC1") (pin "14") (pinfunction "NC_14") (pintype "passive"))
    )
    (net (code "100") (name "unconnected-(HC1-PCM_CLK-Pad5)") (class "Default")
      (node (ref "HC1") (pin "5") (pinfunction "PCM_CLK_5") (pintype "passive"))
    )
    (net (code "101") (name "unconnected-(HC1-PCM_IN-Pad7)") (class "Default")
      (node (ref "HC1") (pin "7") (pinfunction "PCM_IN_7") (pintype "passive"))
    )
    (net (code "102") (name "unconnected-(HC1-PCM_OUT-Pad6)") (class "Default")
      (node (ref "HC1") (pin "6") (pinfunction "PCM_OUT_6") (pintype "passive"))
    )
    (net (code "103") (name "unconnected-(HC1-PCM_SYNC-Pad8)") (class "Default")
      (node (ref "HC1") (pin "8") (pinfunction "PCM_SYNC_8") (pintype "passive"))
    )
    (net (code "104") (name "unconnected-(HC1-PIO0-Pad23)") (class "Default")
      (node (ref "HC1") (pin "23") (pinfunction "PIO0_23") (pintype "passive"))
    )
    (net (code "105") (name "unconnected-(HC1-PIO2-Pad25)") (class "Default")
      (node (ref "HC1") (pin "25") (pinfunction "PIO2_25") (pintype "passive"))
    )
    (net (code "106") (name "unconnected-(HC1-PIO3-Pad26)") (class "Default")
      (node (ref "HC1") (pin "26") (pinfunction "PIO3_26") (pintype "passive"))
    )
    (net (code "107") (name "unconnected-(HC1-PIO4-Pad27)") (class "Default")
      (node (ref "HC1") (pin "27") (pinfunction "PIO4_27") (pintype "passive"))
    )
    (net (code "108") (name "unconnected-(HC1-PIO5-Pad28)") (class "Default")
      (node (ref "HC1") (pin "28") (pinfunction "PIO5_28") (pintype "passive"))
    )
    (net (code "109") (name "unconnected-(HC1-PIO6-Pad29)") (class "Default")
      (node (ref "HC1") (pin "29") (pinfunction "PIO6_29") (pintype "passive"))
    )
    (net (code "110") (name "unconnected-(HC1-PIO7-Pad30)") (class "Default")
      (node (ref "HC1") (pin "30") (pinfunction "PIO7_30") (pintype "passive"))
    )
    (net (code "111") (name "unconnected-(HC1-PIO9-Pad32)") (class "Default")
      (node (ref "HC1") (pin "32") (pinfunction "PIO9_32") (pintype "passive"))
    )
    (net (code "112") (name "unconnected-(HC1-PIO10-Pad33)") (class "Default")
      (node (ref "HC1") (pin "33") (pinfunction "PIO10_33") (pintype "passive"))
    )
    (net (code "113") (name "unconnected-(HC1-RTS-Pad4)") (class "Default")
      (node (ref "HC1") (pin "4") (pinfunction "RTS_4") (pintype "passive"))
    )
    (net (code "114") (name "unconnected-(HC1-USB_D+-Pad20)") (class "Default")
      (node (ref "HC1") (pin "20") (pinfunction "USB_D+_20") (pintype "passive"))
    )
    (net (code "115") (name "unconnected-(HC1-USB_D--Pad15)") (class "Default")
      (node (ref "HC1") (pin "15") (pinfunction "USB_D-_15") (pintype "passive"))
    )
    (net (code "116") (name "unconnected-(K1-PadO1)") (class "Default")
      (node (ref "K1") (pin "O1") (pinfunction "O1_O1") (pintype "passive"))
    )
    (net (code "117") (name "unconnected-(K1-PadO2)") (class "Default")
      (node (ref "K1") (pin "O2") (pinfunction "O2_O2") (pintype "passive"))
    )
    (net (code "118") (name "unconnected-(P5-Pad2)") (class "Default")
      (node (ref "P5") (pin "2") (pinfunction "2_2") (pintype "passive"))
    )
    (net (code "119") (name "unconnected-(P900-Pad3)") (class "Default")
      (node (ref "P900") (pin "3") (pinfunction "3_3") (pintype "passive"))
    )
    (net (code "120") (name "unconnected-(POWER SW-Pad1)") (class "Default")
      (node (ref "POWER SW") (pin "1") (pintype "passive"))
    )
    (net (code "121") (name "unconnected-(U2-PB3_(MISO)-Pad13)") (class "Default")
      (node (ref "U2") (pin "13") (pinfunction "PB3_(MISO)_13") (pintype "bidirectional"))
    )
    (net (code "122") (name "unconnected-(U2-PB4_(OC0)-Pad14)") (class "Default")
      (node (ref "U2") (pin "14") (pinfunction "PB4_(OC0)_14") (pintype "bidirectional"))
    )
    (net (code "123") (name "unconnected-(U2-PB5_(OC1A)-Pad15)") (class "Default")
      (node (ref "U2") (pin "15") (pinfunction "PB5_(OC1A)_15") (pintype "bidirectional"))
    )
    (net (code "124") (name "unconnected-(U2-PB6_(OC1B)-Pad16)") (class "Default")
      (node (ref "U2") (pin "16") (pinfunction "PB6_(OC1B)_16") (pintype "bidirectional"))
    )
    (net (code "125") (name "unconnected-(U2-PB7_(OC2{slash}OC1C)-Pad17)") (class "Default")
      (node (ref "U2") (pin "17") (pinfunction "PB7_(OC2/OC1C)_17") (pintype "bidirectional"))
    )
    (net (code "126") (name "unconnected-(U2-PC1_(A9)-Pad36)") (class "Default")
      (node (ref "U2") (pin "36") (pinfunction "PC1_(A9)_36") (pintype "bidirectional"))
    )
    (net (code "127") (name "unconnected-(U2-PC2_(A10-Pad37)") (class "Default")
      (node (ref "U2") (pin "37") (pinfunction "PC2_(A10_37") (pintype "bidirectional"))
    )
  )
)
